# PultPowerCommutation.net
KiCad netlist of a schematic drawn in EAGLE
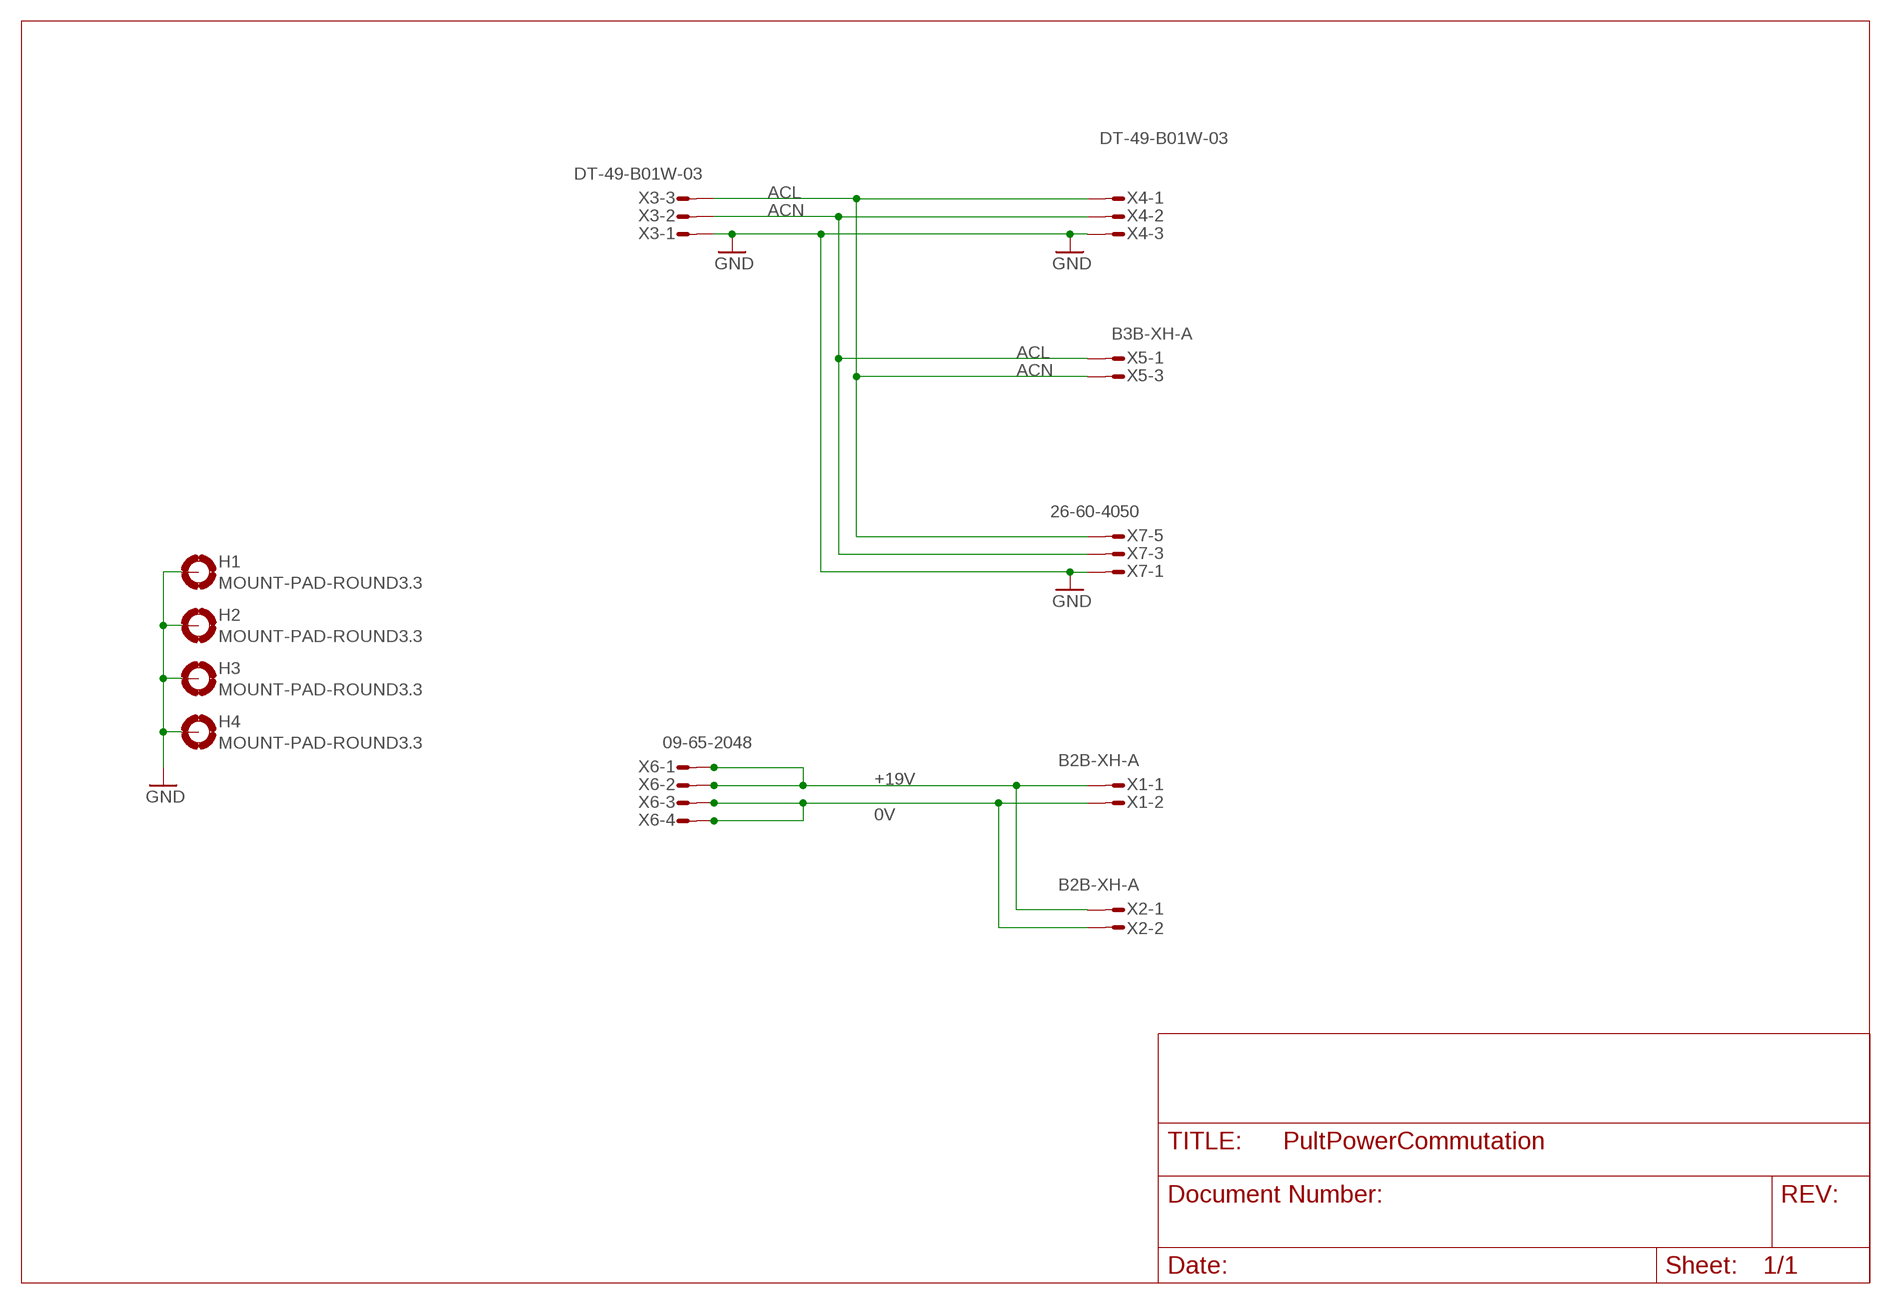
[diagram p0: schematic, sheet 1]

(export (version "E")
  (design (tool "Eeschema 10.0.6"))
  (components
    (comp (ref "H1")
      (value "MOUNT-PAD-ROUND3.3")
      (footprint "eagle-import:3,3-PAD")
      (libsource (lib "eagle-import") (part "MOUNT-PAD-ROUND3.3"))
    )
    (comp (ref "H2")
      (value "MOUNT-PAD-ROUND3.3")
      (footprint "eagle-import:3,3-PAD")
      (libsource (lib "eagle-import") (part "MOUNT-PAD-ROUND3.3"))
    )
    (comp (ref "H3")
      (value "MOUNT-PAD-ROUND3.3")
      (footprint "eagle-import:3,3-PAD")
      (libsource (lib "eagle-import") (part "MOUNT-PAD-ROUND3.3"))
    )
    (comp (ref "H4")
      (value "MOUNT-PAD-ROUND3.3")
      (footprint "eagle-import:3,3-PAD")
      (libsource (lib "eagle-import") (part "MOUNT-PAD-ROUND3.3"))
    )
    (comp (ref "X1")
      (value "B2B-XH-A")
      (footprint "eagle-import:B2B-XH-AM")
      (libsource (lib "eagle-import") (part "B2B-XH-A(M)"))
    )
    (comp (ref "X2")
      (value "B2B-XH-A")
      (footprint "eagle-import:B2B-XH-AM")
      (libsource (lib "eagle-import") (part "B2B-XH-A(M)"))
    )
    (comp (ref "X3")
      (value "DT-49-B01W-03")
      (footprint "eagle-import:DINKLE_DT-49-B01W-03")
      (libsource (lib "eagle-import") (part "DINKLE_DT-49-B01W-03"))
    )
    (comp (ref "X4")
      (value "DT-49-B01W-03")
      (footprint "eagle-import:DINKLE_DT-49-B01W-03")
      (libsource (lib "eagle-import") (part "DINKLE_DT-49-B01W-03"))
    )
    (comp (ref "X5")
      (value "B3B-XH-A")
      (footprint "eagle-import:B3B-XH-AM")
      (libsource (lib "eagle-import") (part "B3B-XH-A(M)"))
    )
    (comp (ref "X6")
      (value "09-65-2048")
      (footprint "eagle-import:MOLEX_09-65-2048")
      (libsource (lib "eagle-import") (part "MOLEX_09-65-2048"))
    )
    (comp (ref "X7")
      (value "26-60-4050")
      (footprint "eagle-import:MOLEX_26-60-4050")
      (libsource (lib "eagle-import") (part "MOLEX_26-60-4050"))
    )
  )
  (nets
    (net (code "1") (name "/+19V") (class "Default")
      (node (ref "X1") (pin "1") (pinfunction "S_1") (pintype "passive"))
      (node (ref "X2") (pin "1") (pinfunction "S_1") (pintype "passive"))
      (node (ref "X6") (pin "1") (pinfunction "S_1") (pintype "passive"))
      (node (ref "X6") (pin "2") (pinfunction "S_2") (pintype "passive"))
    )
    (net (code "2") (name "/0V") (class "Default")
      (node (ref "X1") (pin "2") (pinfunction "S_2") (pintype "passive"))
      (node (ref "X2") (pin "2") (pinfunction "S_2") (pintype "passive"))
      (node (ref "X6") (pin "3") (pinfunction "S_3") (pintype "passive"))
      (node (ref "X6") (pin "4") (pinfunction "S_4") (pintype "passive"))
    )
    (net (code "3") (name "/ACL") (class "Default")
      (node (ref "X3") (pin "3") (pinfunction "S_3") (pintype "passive"))
      (node (ref "X4") (pin "1") (pinfunction "S_1") (pintype "passive"))
      (node (ref "X5") (pin "3") (pinfunction "S_3") (pintype "passive"))
      (node (ref "X7") (pin "5") (pinfunction "S_5") (pintype "passive"))
    )
    (net (code "4") (name "/ACN") (class "Default")
      (node (ref "X3") (pin "2") (pinfunction "S_2") (pintype "passive"))
      (node (ref "X4") (pin "2") (pinfunction "S_2") (pintype "passive"))
      (node (ref "X5") (pin "1") (pinfunction "S_1") (pintype "passive"))
      (node (ref "X7") (pin "3") (pinfunction "S_3") (pintype "passive"))
    )
    (net (code "5") (name "GND") (class "Default")
      (node (ref "H1") (pin "B3,3") (pinfunction "MOUNT_B3,3") (pintype "passive"))
      (node (ref "H2") (pin "B3,3") (pinfunction "MOUNT_B3,3") (pintype "passive"))
      (node (ref "H3") (pin "B3,3") (pinfunction "MOUNT_B3,3") (pintype "passive"))
      (node (ref "H4") (pin "B3,3") (pinfunction "MOUNT_B3,3") (pintype "passive"))
      (node (ref "X3") (pin "1") (pinfunction "S_1") (pintype "passive"))
      (node (ref "X4") (pin "3") (pinfunction "S_3") (pintype "passive"))
      (node (ref "X7") (pin "1") (pinfunction "S_1") (pintype "passive"))
    )
  )
)
